# Sheet_1.net
KiCad netlist of a schematic drawn in Altium Designer
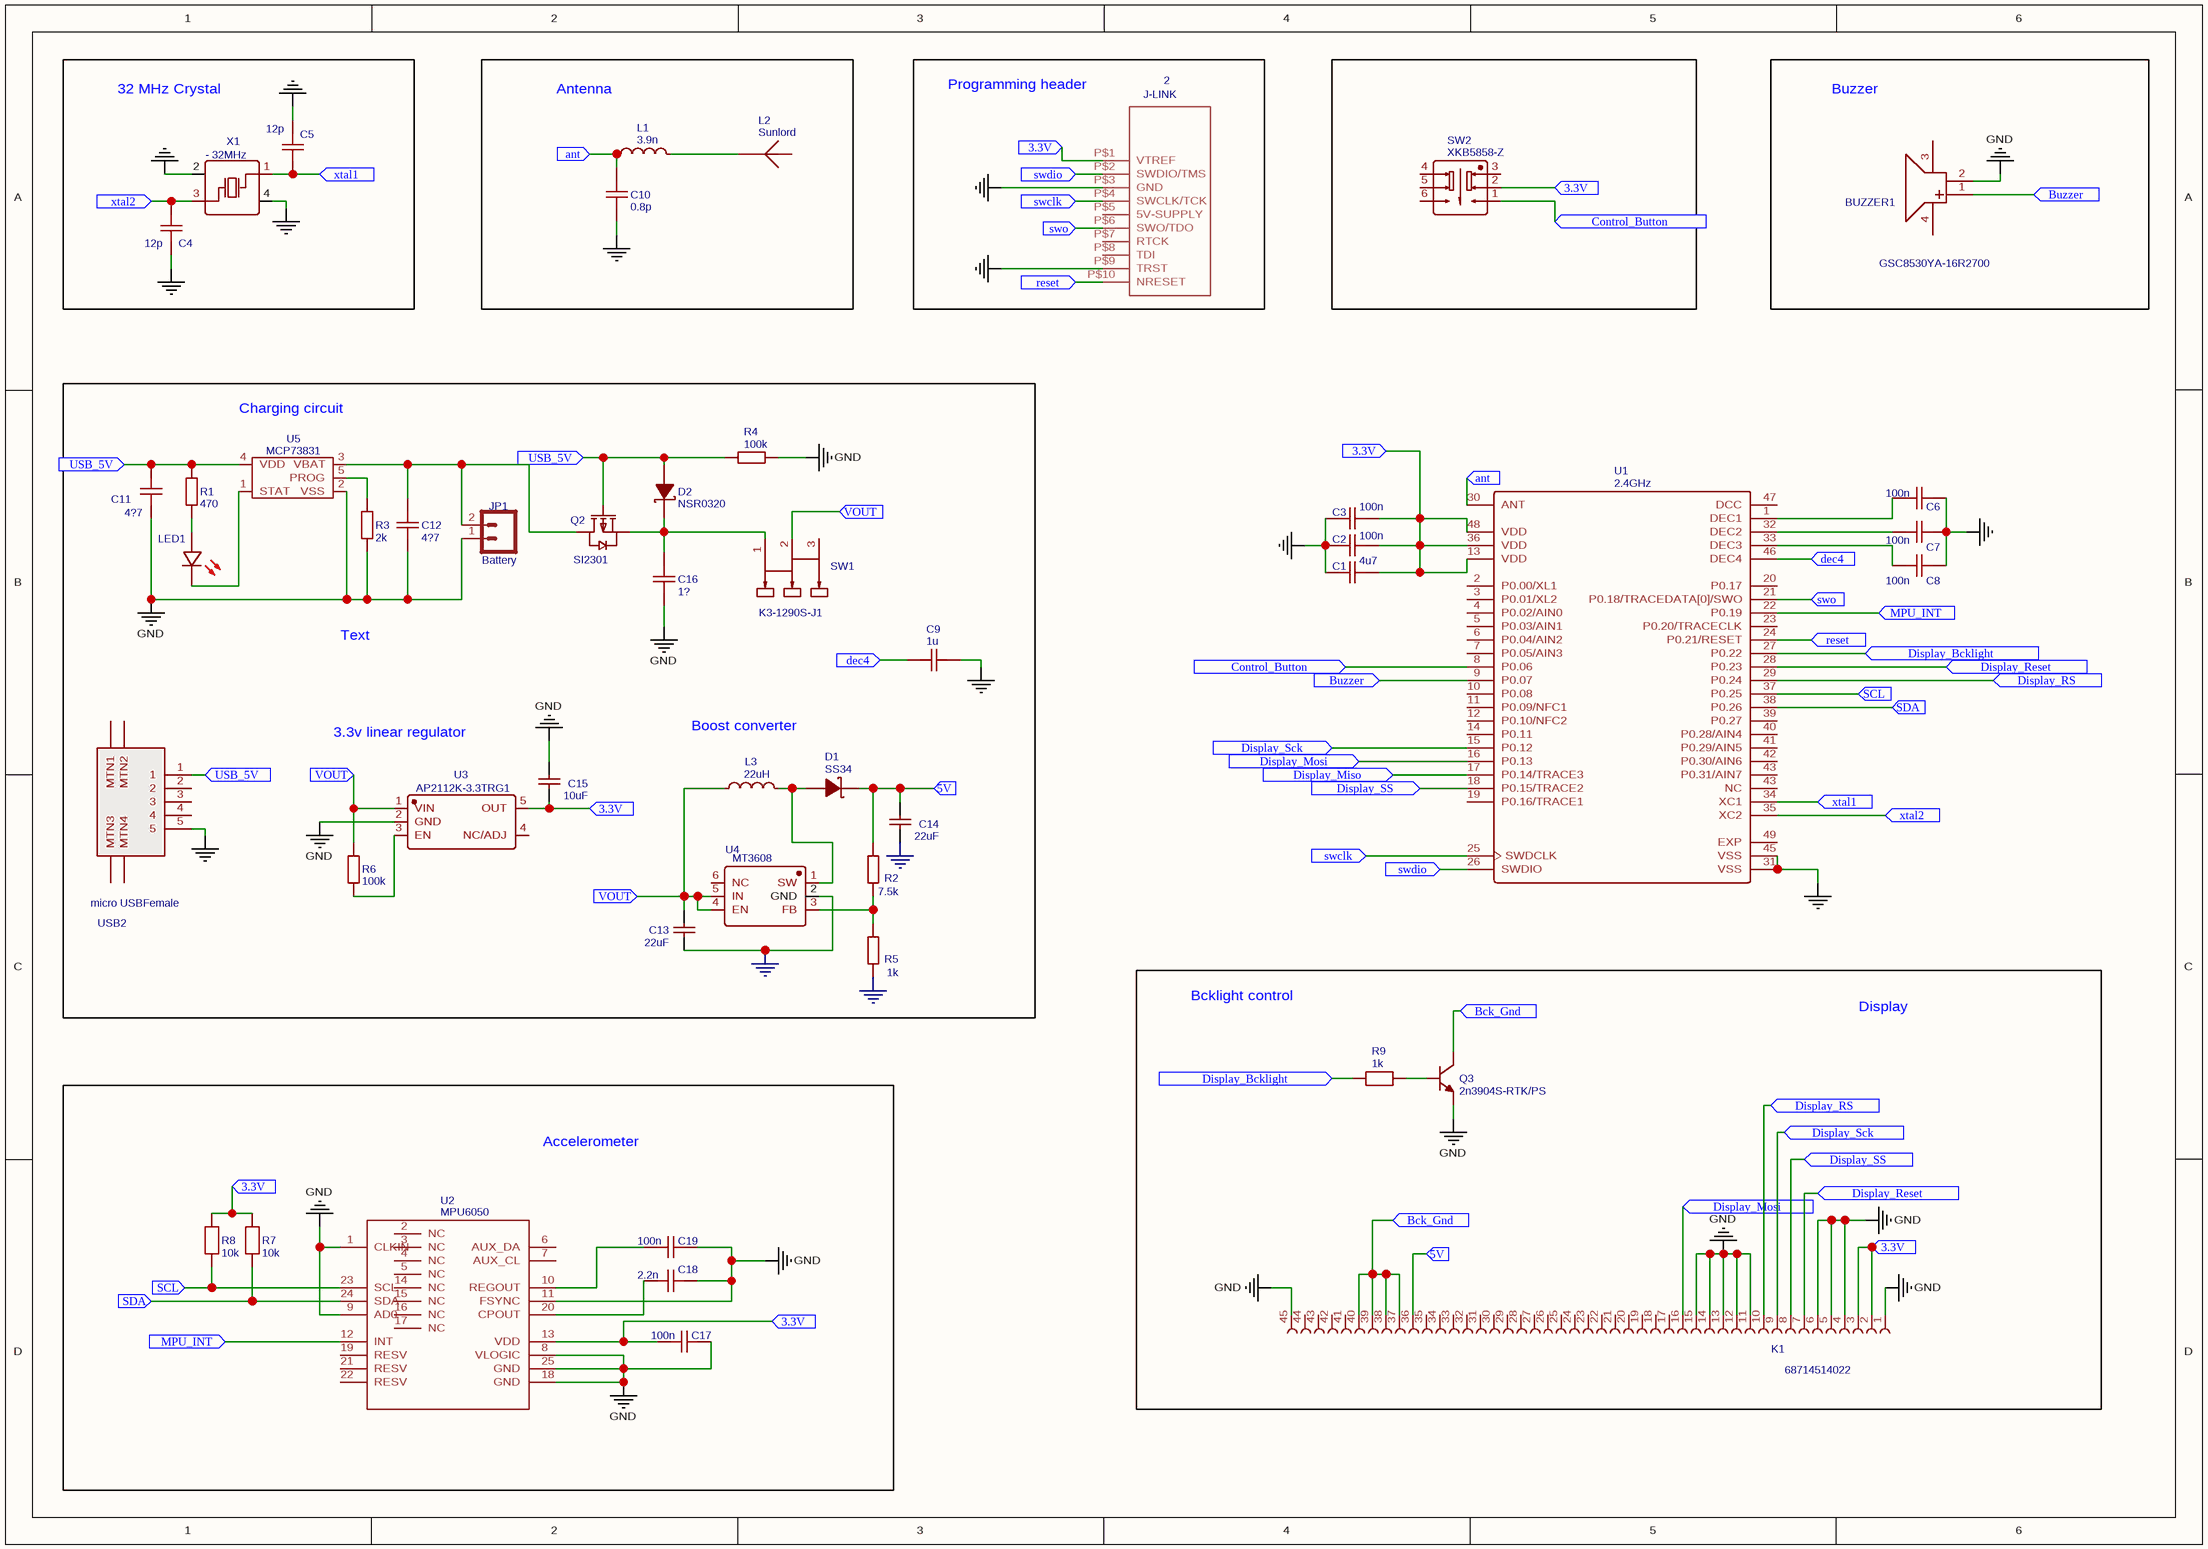
[diagram p0: Sheet_1.schdoc]

(export (version "E")
  (design (tool "Eeschema 10.0.6"))
  (components
    (comp (ref "2")
      (value "J-LINK")
      (fields (field (name "BOM_MANUFACTURER PART") "?") (field (name "CONTRIBUTOR") "Andrew D~{a}'Casto"))
      (libsource (lib "altium-import") (part "root_0_J-LINK_"))
    )
    (comp (ref "BUZZER1")
      (value "GSC8530YA-16R2700")
      (fields (field (name "BOM_SUPPLIER PART") "C255316") (field (name "CONTRIBUTOR") "LCSC"))
      (libsource (lib "altium-import") (part "root_0_GSC8530YA-16R2700_"))
    )
    (comp (ref "C1")
      (value "4u7")
      (fields (field (name "BOM_MANUFACTURER PART") "?"))
      (libsource (lib "altium-import") (part "root_3_4u7_"))
    )
    (comp (ref "C2")
      (value "100n")
      (fields (field (name "BOM_MANUFACTURER PART") "?"))
      (libsource (lib "altium-import") (part "root_3_100n_"))
    )
    (comp (ref "C3")
      (value "100n")
      (fields (field (name "BOM_MANUFACTURER PART") "?"))
      (libsource (lib "altium-import") (part "root_3_100n_"))
    )
    (comp (ref "C4")
      (value "12p")
      (fields (field (name "BOM_MANUFACTURER PART") "?"))
      (libsource (lib "altium-import") (part "root_0_12p_"))
    )
    (comp (ref "C5")
      (value "12p")
      (fields (field (name "BOM_MANUFACTURER PART") "?"))
      (libsource (lib "altium-import") (part "root_0_12p_"))
    )
    (comp (ref "C6")
      (value "100n")
      (fields (field (name "BOM_MANUFACTURER PART") "?"))
      (libsource (lib "altium-import") (part "root_1_100n_"))
    )
    (comp (ref "C7")
      (value "100n")
      (fields (field (name "BOM_MANUFACTURER PART") "?"))
      (libsource (lib "altium-import") (part "root_1_100n_"))
    )
    (comp (ref "C8")
      (value "100n")
      (fields (field (name "BOM_MANUFACTURER PART") "?"))
      (libsource (lib "altium-import") (part "root_1_100n_"))
    )
    (comp (ref "C9")
      (value "1u")
      (fields (field (name "BOM_MANUFACTURER PART") "?"))
      (libsource (lib "altium-import") (part "root_3_1u_"))
    )
    (comp (ref "C10")
      (value "0.8p")
      (fields (field (name "BOM_MANUFACTURER PART") "?"))
      (libsource (lib "altium-import") (part "root_0_0.8p_"))
    )
    (comp (ref "C11")
      (value "4?7")
      (fields (field (name "BOM_MANUFACTURER PART") "?"))
      (libsource (lib "altium-import") (part "root_0_4?7_"))
    )
    (comp (ref "C12")
      (value "4?7")
      (fields (field (name "BOM_MANUFACTURER PART") "?"))
      (libsource (lib "altium-import") (part "root_0_4?7_"))
    )
    (comp (ref "C13")
      (value "22uF")
      (fields
        (field (name "VOLTAGE") "25V")
        (field (name "TOLERANCE") "±10%")
        (field (name "BOM_MANUFACTURER PART") "1812X226K250NT")
      )
      (libsource (lib "altium-import") (part "root_1_22uF_"))
    )
    (comp (ref "C14")
      (value "22uF")
      (fields
        (field (name "VOLTAGE") "25V")
        (field (name "TOLERANCE") "±10%")
        (field (name "BOM_MANUFACTURER PART") "1812X226K250NT")
      )
      (libsource (lib "altium-import") (part "root_3_22uF_"))
    )
    (comp (ref "C15")
      (value "10uF")
      (fields
        (field (name "VOLTAGE") "25V")
        (field (name "TOLERANCE") "±10%")
        (field (name "BOM_MANUFACTURER PART") "1812X226K250NT")
      )
      (libsource (lib "altium-import") (part "root_3_10uF_"))
    )
    (comp (ref "C16")
      (value "1?")
      (fields (field (name "BOM_MANUFACTURER PART") "?"))
      (libsource (lib "altium-import") (part "root_0_1?_"))
    )
    (comp (ref "C17")
      (value "100n")
      (fields (field (name "BOM_MANUFACTURER PART") "?"))
      (libsource (lib "altium-import") (part "root_1_100n_"))
    )
    (comp (ref "C18")
      (value "2.2n")
      (fields (field (name "BOM_MANUFACTURER PART") "?"))
      (libsource (lib "altium-import") (part "root_1_2.2n_"))
    )
    (comp (ref "C19")
      (value "100n")
      (fields (field (name "BOM_MANUFACTURER PART") "?"))
      (libsource (lib "altium-import") (part "root_1_100n_"))
    )
    (comp (ref "D1")
      (value "SS34")
      (fields (field (name "BOM_SUPPLIER PART") "C8678"))
      (libsource (lib "altium-import") (part "root_0_SS34_"))
    )
    (comp (ref "D2")
      (value "NSR0320")
      (fields (field (name "BOM_MANUFACTURER PART") "?"))
      (libsource (lib "altium-import") (part "root_3_NSR0320_"))
    )
    (comp (ref "JP1")
      (value "Battery")
      (fields (field (name "BOM_MANUFACTURER PART") "?") (field (name "CONTRIBUTOR") "SparkFun"))
      (libsource (lib "altium-import") (part "root_2_Battery_"))
    )
    (comp (ref "K1")
      (value "68714514022")
      (description "WR-FPC 0.5mm SMT ZIF Horizontal Top Contact, 45 Pins=Code : Con_FPC_ZIF_0.50_68714514022")
      (fields (field (name "BOM_MANUFACTURER PART") "?"))
      (libsource (lib "altium-import") (part "root_3_68714514022_"))
    )
    (comp (ref "L1")
      (value "3.9n")
      (fields (field (name "BOM_MANUFACTURER PART") "?"))
      (libsource (lib "altium-import") (part "root_0_3.9n_"))
    )
    (comp (ref "L2")
      (value "Sunlord")
      (fields
        (field (name "BOM_SUPPLIER PART") "C279814")
        (field (name "BOM_MANUFACTURER PART") "SLDA52-2R540G-S1TF")
        (field (name "CONTRIBUTOR") "LCSC")
      )
      (libsource (lib "altium-import") (part "root_3_Sunlord_"))
    )
    (comp (ref "L3")
      (value "22uH")
      (fields
        (field (name "BOM_MANUFACTURER PART") "SMRH74-220MT")
        (field (name "BOM_SUPPLIER PART") "C27442")
      )
      (libsource (lib "altium-import") (part "root_0_22uH_"))
    )
    (comp (ref "LED1")
      (value "charge")
      (fields
        (field (name "BOM_SUPPLIER PART") "C131244")
        (field (name "BOM_MANUFACTURER PART") "17-21SURC/S530-A2/TR8")
      )
      (libsource (lib "altium-import") (part "root_3_charge_"))
    )
    (comp (ref "Q2") (value "SI2301") (libsource (lib "altium-import") (part "root_3_SI2301_")))
    (comp (ref "Q3")
      (value "2n3904S-RTK/PS")
      (fields (field (name "BOM_SUPPLIER PART") "C18536"))
      (libsource (lib "altium-import") (part "root_0_2n3904S-RTK/PS_"))
    )
    (comp (ref "R1")
      (value "470")
      (fields (field (name "BOM_MANUFACTURER PART") "?"))
      (libsource (lib "altium-import") (part "root_1_470_"))
    )
    (comp (ref "R2")
      (value "7.5k")
      (fields (field (name "BOM_MANUFACTURER PART") "?"))
      (libsource (lib "altium-import") (part "root_1_7.5k_"))
    )
    (comp (ref "R3")
      (value "2k")
      (fields (field (name "BOM_MANUFACTURER PART") "?"))
      (libsource (lib "altium-import") (part "root_1_2k_"))
    )
    (comp (ref "R4")
      (value "100k")
      (fields (field (name "BOM_MANUFACTURER PART") "?"))
      (libsource (lib "altium-import") (part "root_2_100k_"))
    )
    (comp (ref "R5")
      (value "1k")
      (fields (field (name "BOM_MANUFACTURER PART") "?"))
      (libsource (lib "altium-import") (part "root_1_1k_"))
    )
    (comp (ref "R6")
      (value "100k")
      (fields (field (name "BOM_MANUFACTURER PART") "?"))
      (libsource (lib "altium-import") (part "root_3_100k_"))
    )
    (comp (ref "R7")
      (value "10k")
      (fields (field (name "BOM_MANUFACTURER PART") "?"))
      (libsource (lib "altium-import") (part "root_1_10k_"))
    )
    (comp (ref "R8")
      (value "10k")
      (fields (field (name "BOM_MANUFACTURER PART") "?"))
      (libsource (lib "altium-import") (part "root_1_10k_"))
    )
    (comp (ref "R9")
      (value "1k")
      (fields (field (name "BOM_MANUFACTURER PART") "?"))
      (libsource (lib "altium-import") (part "root_0_1k_"))
    )
    (comp (ref "SW1")
      (value "K3-1290S-J1")
      (fields (field (name "BOM_SUPPLIER PART") "C223846") (field (name "CONTRIBUTOR") "LCSC"))
      (libsource (lib "altium-import") (part "root_0_K3-1290S-J1_"))
    )
    (comp (ref "SW2")
      (value "XKB5858-Z")
      (fields (field (name "BOM_SUPPLIER PART") "C318868") (field (name "CONTRIBUTOR") "LCSC"))
      (libsource (lib "altium-import") (part "root_1_XKB5858-Z_"))
    )
    (comp (ref "U1")
      (value "2.4GHz")
      (fields
        (field (name "BOM_MANUFACTURER PART") "NRF52832-QFAA-R")
        (field (name "BOM_SUPPLIER PART") "C77540")
      )
      (libsource (lib "altium-import") (part "root_0_2.4GHz_"))
    )
    (comp (ref "U2")
      (value "MPU6050")
      (fields (field (name "BOM_MANUFACTURER PART") "?"))
      (libsource (lib "altium-import") (part "root_0_MPU6050_"))
    )
    (comp (ref "U3")
      (value "AP2112K-3.3TRG1")
      (fields (field (name "BOM_SUPPLIER PART") "C51118") (field (name "CONTRIBUTOR") "LCSC"))
      (libsource (lib "altium-import") (part "root_0_AP2112K-3.3TRG1_"))
    )
    (comp (ref "U4")
      (value "MT3608")
      (fields (field (name "BOM_SUPPLIER PART") "C84817"))
      (libsource (lib "altium-import") (part "root_0_MT3608_"))
    )
    (comp (ref "U5")
      (value "MCP73831")
      (fields (field (name "BOM_MANUFACTURER PART") "?") (field (name "CONTRIBUTOR") "KiCad"))
      (libsource (lib "altium-import") (part "root_0_MCP73831_"))
    )
    (comp (ref "USB2")
      (value "micro USBFemale")
      (fields (field (name "BOM_SUPPLIER PART") "C10418"))
      (libsource (lib "altium-import") (part "root_0_micro USBFemale_"))
    )
    (comp (ref "X1")
      (value "- 32MHz")
      (fields
        (field (name "BOM_SUPPLIER PART") "C253733")
        (field (name "BOM_MANUFACTURER PART") "1XTV26000PEA")
        (field (name "CONTRIBUTOR") "LCSC")
      )
      (libsource (lib "altium-import") (part "root_2_- 32MHz_"))
    )
  )
  (nets
    (net (code "1") (name "/3.3V") (class "Default")
      (node (ref "2") (pin "P$1") (pinfunction "VTREF_P$1") (pintype "passive"))
      (node (ref "C1") (pin "2") (pinfunction "2_2") (pintype "passive"))
      (node (ref "C15") (pin "2") (pinfunction "2_2") (pintype "passive"))
      (node (ref "C17") (pin "2") (pinfunction "2_2") (pintype "passive"))
      (node (ref "C2") (pin "2") (pinfunction "2_2") (pintype "passive"))
      (node (ref "C3") (pin "2") (pinfunction "2_2") (pintype "passive"))
      (node (ref "K1") (pin "2") (pinfunction "2_2") (pintype "passive"))
      (node (ref "K1") (pin "3") (pinfunction "3_3") (pintype "passive"))
      (node (ref "R7") (pin "2") (pinfunction "2_2") (pintype "passive"))
      (node (ref "R8") (pin "2") (pinfunction "2_2") (pintype "passive"))
      (node (ref "SW2") (pin "2") (pinfunction "2_2") (pintype "passive"))
      (node (ref "U1") (pin "13") (pinfunction "VDD_13") (pintype "passive"))
      (node (ref "U1") (pin "36") (pinfunction "VDD_36") (pintype "passive"))
      (node (ref "U1") (pin "48") (pinfunction "VDD_48") (pintype "passive"))
      (node (ref "U2") (pin "13") (pinfunction "VDD_13") (pintype "passive"))
      (node (ref "U3") (pin "5") (pinfunction "OUT_5") (pintype "passive"))
    )
    (net (code "2") (name "/5V") (class "Default")
      (node (ref "C14") (pin "1") (pinfunction "1_1") (pintype "passive"))
      (node (ref "D1") (pin "2") (pinfunction "K_2") (pintype "passive"))
      (node (ref "K1") (pin "36") (pinfunction "36_36") (pintype "passive"))
      (node (ref "R2") (pin "2") (pinfunction "2_2") (pintype "passive"))
    )
    (net (code "3") (name "/Bck_Gnd") (class "Default")
      (node (ref "K1") (pin "37") (pinfunction "37_37") (pintype "passive"))
      (node (ref "K1") (pin "38") (pinfunction "38_38") (pintype "passive"))
      (node (ref "K1") (pin "39") (pinfunction "39_39") (pintype "passive"))
      (node (ref "K1") (pin "40") (pinfunction "40_40") (pintype "passive"))
      (node (ref "Q3") (pin "3") (pinfunction "C_3") (pintype "passive"))
    )
    (net (code "4") (name "/Buzzer") (class "Default")
      (node (ref "BUZZER1") (pin "1") (pinfunction "+_1") (pintype "passive"))
      (node (ref "U1") (pin "9") (pinfunction "P0.07_9") (pintype "passive"))
    )
    (net (code "5") (name "/Control_Button") (class "Default")
      (node (ref "SW2") (pin "1") (pinfunction "1_1") (pintype "passive"))
      (node (ref "U1") (pin "8") (pinfunction "P0.06_8") (pintype "passive"))
    )
    (net (code "6") (name "/Display_Bcklight") (class "Default")
      (node (ref "R9") (pin "1") (pinfunction "1_1") (pintype "passive"))
      (node (ref "U1") (pin "27") (pinfunction "P0.22_27") (pintype "passive"))
    )
    (net (code "7") (name "/Display_Miso") (class "Default")
      (node (ref "U1") (pin "17") (pinfunction "P0.14/TRACE3_17") (pintype "passive"))
    )
    (net (code "8") (name "/Display_Mosi") (class "Default")
      (node (ref "K1") (pin "16") (pinfunction "16_16") (pintype "passive"))
      (node (ref "U1") (pin "16") (pinfunction "P0.13_16") (pintype "passive"))
    )
    (net (code "9") (name "/Display_RS") (class "Default")
      (node (ref "K1") (pin "10") (pinfunction "10_10") (pintype "passive"))
      (node (ref "U1") (pin "29") (pinfunction "P0.24_29") (pintype "passive"))
    )
    (net (code "10") (name "/Display_Reset") (class "Default")
      (node (ref "K1") (pin "7") (pinfunction "7_7") (pintype "passive"))
      (node (ref "U1") (pin "28") (pinfunction "P0.23_28") (pintype "passive"))
    )
    (net (code "11") (name "/Display_SS") (class "Default")
      (node (ref "K1") (pin "8") (pinfunction "8_8") (pintype "passive"))
      (node (ref "U1") (pin "18") (pinfunction "P0.15/TRACE2_18") (pintype "passive"))
    )
    (net (code "12") (name "/Display_Sck") (class "Default")
      (node (ref "K1") (pin "9") (pinfunction "9_9") (pintype "passive"))
      (node (ref "U1") (pin "15") (pinfunction "P0.12_15") (pintype "passive"))
    )
    (net (code "13") (name "/MPU_INT") (class "Default")
      (node (ref "U1") (pin "22") (pinfunction "P0.19_22") (pintype "passive"))
      (node (ref "U2") (pin "12") (pinfunction "INT_12") (pintype "passive"))
    )
    (net (code "14") (name "/SCL") (class "Default")
      (node (ref "R8") (pin "1") (pinfunction "1_1") (pintype "passive"))
      (node (ref "U1") (pin "37") (pinfunction "P0.25_37") (pintype "passive"))
      (node (ref "U2") (pin "23") (pinfunction "SCL_23") (pintype "passive"))
    )
    (net (code "15") (name "/SDA") (class "Default")
      (node (ref "R7") (pin "1") (pinfunction "1_1") (pintype "passive"))
      (node (ref "U1") (pin "38") (pinfunction "P0.26_38") (pintype "passive"))
      (node (ref "U2") (pin "24") (pinfunction "SDA_24") (pintype "passive"))
    )
    (net (code "16") (name "/USB_5V") (class "Default")
      (node (ref "C11") (pin "2") (pinfunction "2_2") (pintype "passive"))
      (node (ref "D2") (pin "1") (pinfunction "A_1") (pintype "passive"))
      (node (ref "Q2") (pin "1") (pinfunction "G_1") (pintype "passive"))
      (node (ref "R1") (pin "2") (pinfunction "2_2") (pintype "passive"))
      (node (ref "R4") (pin "2") (pinfunction "2_2") (pintype "passive"))
      (node (ref "U5") (pin "4") (pinfunction "VDD_4") (pintype "passive"))
      (node (ref "USB2") (pin "1") (pinfunction "1_1") (pintype "passive"))
    )
    (net (code "17") (name "/VOUT") (class "Default")
      (node (ref "C13") (pin "2") (pinfunction "2_2") (pintype "passive"))
      (node (ref "L3") (pin "1") (pinfunction "1_1") (pintype "passive"))
      (node (ref "R6") (pin "1") (pinfunction "1_1") (pintype "passive"))
      (node (ref "SW1") (pin "2") (pinfunction "2_2") (pintype "passive"))
      (node (ref "U3") (pin "1") (pinfunction "VIN_1") (pintype "passive"))
      (node (ref "U4") (pin "4") (pinfunction "EN_4") (pintype "passive"))
      (node (ref "U4") (pin "5") (pinfunction "IN_5") (pintype "passive"))
    )
    (net (code "18") (name "/ant") (class "Default")
      (node (ref "C10") (pin "2") (pinfunction "2_2") (pintype "passive"))
      (node (ref "L1") (pin "1") (pinfunction "1_1") (pintype "passive"))
      (node (ref "U1") (pin "30") (pinfunction "ANT_30") (pintype "passive"))
    )
    (net (code "19") (name "/dec4") (class "Default")
      (node (ref "C9") (pin "1") (pinfunction "1_1") (pintype "passive"))
      (node (ref "U1") (pin "46") (pinfunction "DEC4_46") (pintype "passive"))
    )
    (net (code "20") (name "/reset") (class "Default")
      (node (ref "2") (pin "P$10") (pinfunction "NRESET_P$10") (pintype "passive"))
      (node (ref "U1") (pin "24") (pinfunction "P0.21/RESET_24") (pintype "passive"))
    )
    (net (code "21") (name "/swclk") (class "Default")
      (node (ref "2") (pin "P$4") (pinfunction "SWCLK/TCK_P$4") (pintype "passive"))
      (node (ref "U1") (pin "25") (pinfunction "SWDCLK_25") (pintype "passive"))
    )
    (net (code "22") (name "/swdio") (class "Default")
      (node (ref "2") (pin "P$2") (pinfunction "SWDIO/TMS_P$2") (pintype "passive"))
      (node (ref "U1") (pin "26") (pinfunction "SWDIO_26") (pintype "passive"))
    )
    (net (code "23") (name "/swo") (class "Default")
      (node (ref "2") (pin "P$6") (pinfunction "SWO/TDO_P$6") (pintype "passive"))
      (node (ref "U1") (pin "21") (pinfunction "P0.18/TRACEDATA[0]/SWO_21") (pintype "passive"))
    )
    (net (code "24") (name "/xtal1") (class "Default")
      (node (ref "C5") (pin "1") (pinfunction "1_1") (pintype "passive"))
      (node (ref "U1") (pin "34") (pinfunction "XC1_34") (pintype "passive"))
      (node (ref "X1") (pin "1") (pinfunction "OSC1_1") (pintype "passive"))
    )
    (net (code "25") (name "/xtal2") (class "Default")
      (node (ref "C4") (pin "2") (pinfunction "2_2") (pintype "passive"))
      (node (ref "U1") (pin "35") (pinfunction "XC2_35") (pintype "passive"))
      (node (ref "X1") (pin "3") (pinfunction "OSC2_3") (pintype "passive"))
    )
    (net (code "26") (name "GND") (class "Default")
      (node (ref "2") (pin "P$3") (pinfunction "GND_P$3") (pintype "passive"))
      (node (ref "2") (pin "P$9") (pinfunction "TRST_P$9") (pintype "passive"))
      (node (ref "BUZZER1") (pin "2") (pinfunction "-_2") (pintype "passive"))
      (node (ref "C1") (pin "1") (pinfunction "1_1") (pintype "passive"))
      (node (ref "C10") (pin "1") (pinfunction "1_1") (pintype "passive"))
      (node (ref "C11") (pin "1") (pinfunction "1_1") (pintype "passive"))
      (node (ref "C12") (pin "1") (pinfunction "1_1") (pintype "passive"))
      (node (ref "C13") (pin "1") (pinfunction "1_1") (pintype "passive"))
      (node (ref "C14") (pin "2") (pinfunction "2_2") (pintype "passive"))
      (node (ref "C15") (pin "1") (pinfunction "1_1") (pintype "passive"))
      (node (ref "C16") (pin "1") (pinfunction "1_1") (pintype "passive"))
      (node (ref "C17") (pin "1") (pinfunction "1_1") (pintype "passive"))
      (node (ref "C18") (pin "1") (pinfunction "1_1") (pintype "passive"))
      (node (ref "C19") (pin "1") (pinfunction "1_1") (pintype "passive"))
      (node (ref "C2") (pin "1") (pinfunction "1_1") (pintype "passive"))
      (node (ref "C3") (pin "1") (pinfunction "1_1") (pintype "passive"))
      (node (ref "C4") (pin "1") (pinfunction "1_1") (pintype "passive"))
      (node (ref "C5") (pin "2") (pinfunction "2_2") (pintype "passive"))
      (node (ref "C6") (pin "1") (pinfunction "1_1") (pintype "passive"))
      (node (ref "C7") (pin "1") (pinfunction "1_1") (pintype "passive"))
      (node (ref "C8") (pin "1") (pinfunction "1_1") (pintype "passive"))
      (node (ref "C9") (pin "2") (pinfunction "2_2") (pintype "passive"))
      (node (ref "JP1") (pin "1") (pinfunction "2_1") (pintype "passive"))
      (node (ref "K1") (pin "1") (pinfunction "1_1") (pintype "passive"))
      (node (ref "K1") (pin "11") (pinfunction "11_11") (pintype "passive"))
      (node (ref "K1") (pin "12") (pinfunction "12_12") (pintype "passive"))
      (node (ref "K1") (pin "13") (pinfunction "13_13") (pintype "passive"))
      (node (ref "K1") (pin "14") (pinfunction "14_14") (pintype "passive"))
      (node (ref "K1") (pin "15") (pinfunction "15_15") (pintype "passive"))
      (node (ref "K1") (pin "4") (pinfunction "4_4") (pintype "passive"))
      (node (ref "K1") (pin "45") (pinfunction "45_45") (pintype "passive"))
      (node (ref "K1") (pin "5") (pinfunction "5_5") (pintype "passive"))
      (node (ref "K1") (pin "6") (pinfunction "6_6") (pintype "passive"))
      (node (ref "Q3") (pin "1") (pinfunction "E_1") (pintype "passive"))
      (node (ref "R3") (pin "1") (pinfunction "1_1") (pintype "passive"))
      (node (ref "R4") (pin "1") (pinfunction "1_1") (pintype "passive"))
      (node (ref "R5") (pin "1") (pinfunction "1_1") (pintype "passive"))
      (node (ref "U1") (pin "31") (pinfunction "VSS_31") (pintype "passive"))
      (node (ref "U1") (pin "45") (pinfunction "VSS_45") (pintype "passive"))
      (node (ref "U2") (pin "1") (pinfunction "CLKIN_1") (pintype "passive"))
      (node (ref "U2") (pin "11") (pinfunction "FSYNC_11") (pintype "passive"))
      (node (ref "U2") (pin "18") (pinfunction "GND_18") (pintype "passive"))
      (node (ref "U2") (pin "25") (pinfunction "GND_25") (pintype "passive"))
      (node (ref "U2") (pin "8") (pinfunction "VLOGIC_8") (pintype "passive"))
      (node (ref "U2") (pin "9") (pinfunction "AD0_9") (pintype "passive"))
      (node (ref "U3") (pin "2") (pinfunction "GND_2") (pintype "passive"))
      (node (ref "U4") (pin "2") (pinfunction "GND_2") (pintype "passive"))
      (node (ref "U5") (pin "2") (pinfunction "VSS_2") (pintype "passive"))
      (node (ref "USB2") (pin "5") (pinfunction "5_5") (pintype "passive"))
      (node (ref "X1") (pin "2") (pinfunction "GND_2") (pintype "passive"))
      (node (ref "X1") (pin "4") (pinfunction "GND_4") (pintype "passive"))
    )
    (net (code "27") (name "Net-(D1-A)") (class "Default")
      (node (ref "D1") (pin "1") (pinfunction "A_1") (pintype "passive"))
      (node (ref "L3") (pin "2") (pinfunction "2_2") (pintype "passive"))
      (node (ref "U4") (pin "1") (pinfunction "SW_1") (pintype "passive"))
    )
    (net (code "28") (name "Net-(D2-K)") (class "Default")
      (node (ref "C16") (pin "2") (pinfunction "2_2") (pintype "passive"))
      (node (ref "D2") (pin "2") (pinfunction "K_2") (pintype "passive"))
      (node (ref "Q2") (pin "2") (pinfunction "S_2") (pintype "passive"))
      (node (ref "SW1") (pin "1") (pinfunction "1_1") (pintype "passive"))
    )
    (net (code "29") (name "Net-(JP1-1)") (class "Default")
      (node (ref "C12") (pin "2") (pinfunction "2_2") (pintype "passive"))
      (node (ref "JP1") (pin "2") (pinfunction "1_2") (pintype "passive"))
      (node (ref "Q2") (pin "3") (pinfunction "D_3") (pintype "passive"))
      (node (ref "U5") (pin "3") (pinfunction "VBAT_3") (pintype "passive"))
    )
    (net (code "30") (name "Net-(L1-Pad2)") (class "Default")
      (node (ref "L1") (pin "2") (pinfunction "2_2") (pintype "passive"))
      (node (ref "L2") (pin "ANT") (pinfunction "ANT_ANT") (pintype "passive"))
    )
    (net (code "31") (name "Net-(LED1-+)") (class "Default")
      (node (ref "LED1") (pin "1") (pinfunction "+_1") (pintype "passive"))
      (node (ref "R1") (pin "1") (pinfunction "1_1") (pintype "passive"))
    )
    (net (code "32") (name "Net-(LED1--)") (class "Default")
      (node (ref "LED1") (pin "2") (pinfunction "-_2") (pintype "passive"))
      (node (ref "U5") (pin "1") (pinfunction "STAT_1") (pintype "passive"))
    )
    (net (code "33") (name "Net-(Q3-B)") (class "Default")
      (node (ref "Q3") (pin "2") (pinfunction "B_2") (pintype "passive"))
      (node (ref "R9") (pin "2") (pinfunction "2_2") (pintype "passive"))
    )
    (net (code "34") (name "Net-(U1-DEC1)") (class "Default")
      (node (ref "C6") (pin "2") (pinfunction "2_2") (pintype "passive"))
      (node (ref "U1") (pin "1") (pinfunction "DEC1_1") (pintype "passive"))
    )
    (net (code "35") (name "Net-(U1-DEC2)") (class "Default")
      (node (ref "C7") (pin "2") (pinfunction "2_2") (pintype "passive"))
      (node (ref "U1") (pin "32") (pinfunction "DEC2_32") (pintype "passive"))
    )
    (net (code "36") (name "Net-(U1-DEC3)") (class "Default")
      (node (ref "C8") (pin "2") (pinfunction "2_2") (pintype "passive"))
      (node (ref "U1") (pin "33") (pinfunction "DEC3_33") (pintype "passive"))
    )
    (net (code "37") (name "Net-(U2-CPOUT)") (class "Default")
      (node (ref "C18") (pin "2") (pinfunction "2_2") (pintype "passive"))
      (node (ref "U2") (pin "20") (pinfunction "CPOUT_20") (pintype "passive"))
    )
    (net (code "38") (name "Net-(U2-REGOUT)") (class "Default")
      (node (ref "C19") (pin "2") (pinfunction "2_2") (pintype "passive"))
      (node (ref "U2") (pin "10") (pinfunction "REGOUT_10") (pintype "passive"))
    )
    (net (code "39") (name "Net-(U3-EN)") (class "Default")
      (node (ref "R6") (pin "2") (pinfunction "2_2") (pintype "passive"))
      (node (ref "U3") (pin "3") (pinfunction "EN_3") (pintype "passive"))
    )
    (net (code "40") (name "Net-(U4-FB)") (class "Default")
      (node (ref "R2") (pin "1") (pinfunction "1_1") (pintype "passive"))
      (node (ref "R5") (pin "2") (pinfunction "2_2") (pintype "passive"))
      (node (ref "U4") (pin "3") (pinfunction "FB_3") (pintype "passive"))
    )
    (net (code "41") (name "Net-(U5-PROG)") (class "Default")
      (node (ref "R3") (pin "2") (pinfunction "2_2") (pintype "passive"))
      (node (ref "U5") (pin "5") (pinfunction "PROG_5") (pintype "passive"))
    )
    (net (code "42") (name "unconnected-(2-5V-SUPPLY-PadP$5)") (class "Default")
      (node (ref "2") (pin "P$5") (pinfunction "5V-SUPPLY_P$5") (pintype "passive"))
    )
    (net (code "43") (name "unconnected-(2-RTCK-PadP$7)") (class "Default")
      (node (ref "2") (pin "P$7") (pinfunction "RTCK_P$7") (pintype "passive"))
    )
    (net (code "44") (name "unconnected-(2-TDI-PadP$8)") (class "Default")
      (node (ref "2") (pin "P$8") (pinfunction "TDI_P$8") (pintype "passive"))
    )
    (net (code "45") (name "unconnected-(BUZZER1-Pad3)") (class "Default")
      (node (ref "BUZZER1") (pin "3") (pinfunction "3_3") (pintype "passive"))
    )
    (net (code "46") (name "unconnected-(BUZZER1-Pad4)") (class "Default")
      (node (ref "BUZZER1") (pin "4") (pinfunction "4_4") (pintype "passive"))
    )
    (net (code "47") (name "unconnected-(K1-Pad17)") (class "Default")
      (node (ref "K1") (pin "17") (pinfunction "17_17") (pintype "passive"))
    )
    (net (code "48") (name "unconnected-(K1-Pad18)") (class "Default")
      (node (ref "K1") (pin "18") (pinfunction "18_18") (pintype "passive"))
    )
    (net (code "49") (name "unconnected-(K1-Pad19)") (class "Default")
      (node (ref "K1") (pin "19") (pinfunction "19_19") (pintype "passive"))
    )
    (net (code "50") (name "unconnected-(K1-Pad20)") (class "Default")
      (node (ref "K1") (pin "20") (pinfunction "20_20") (pintype "passive"))
    )
    (net (code "51") (name "unconnected-(K1-Pad21)") (class "Default")
      (node (ref "K1") (pin "21") (pinfunction "21_21") (pintype "passive"))
    )
    (net (code "52") (name "unconnected-(K1-Pad22)") (class "Default")
      (node (ref "K1") (pin "22") (pinfunction "22_22") (pintype "passive"))
    )
    (net (code "53") (name "unconnected-(K1-Pad23)") (class "Default")
      (node (ref "K1") (pin "23") (pinfunction "23_23") (pintype "passive"))
    )
    (net (code "54") (name "unconnected-(K1-Pad24)") (class "Default")
      (node (ref "K1") (pin "24") (pinfunction "24_24") (pintype "passive"))
    )
    (net (code "55") (name "unconnected-(K1-Pad25)") (class "Default")
      (node (ref "K1") (pin "25") (pinfunction "25_25") (pintype "passive"))
    )
    (net (code "56") (name "unconnected-(K1-Pad26)") (class "Default")
      (node (ref "K1") (pin "26") (pinfunction "26_26") (pintype "passive"))
    )
    (net (code "57") (name "unconnected-(K1-Pad27)") (class "Default")
      (node (ref "K1") (pin "27") (pinfunction "27_27") (pintype "passive"))
    )
    (net (code "58") (name "unconnected-(K1-Pad28)") (class "Default")
      (node (ref "K1") (pin "28") (pinfunction "28_28") (pintype "passive"))
    )
    (net (code "59") (name "unconnected-(K1-Pad29)") (class "Default")
      (node (ref "K1") (pin "29") (pinfunction "29_29") (pintype "passive"))
    )
    (net (code "60") (name "unconnected-(K1-Pad30)") (class "Default")
      (node (ref "K1") (pin "30") (pinfunction "30_30") (pintype "passive"))
    )
    (net (code "61") (name "unconnected-(K1-Pad31)") (class "Default")
      (node (ref "K1") (pin "31") (pinfunction "31_31") (pintype "passive"))
    )
    (net (code "62") (name "unconnected-(K1-Pad32)") (class "Default")
      (node (ref "K1") (pin "32") (pinfunction "32_32") (pintype "passive"))
    )
    (net (code "63") (name "unconnected-(K1-Pad33)") (class "Default")
      (node (ref "K1") (pin "33") (pinfunction "33_33") (pintype "passive"))
    )
    (net (code "64") (name "unconnected-(K1-Pad34)") (class "Default")
      (node (ref "K1") (pin "34") (pinfunction "34_34") (pintype "passive"))
    )
    (net (code "65") (name "unconnected-(K1-Pad35)") (class "Default")
      (node (ref "K1") (pin "35") (pinfunction "35_35") (pintype "passive"))
    )
    (net (code "66") (name "unconnected-(K1-Pad41)") (class "Default")
      (node (ref "K1") (pin "41") (pinfunction "41_41") (pintype "passive"))
    )
    (net (code "67") (name "unconnected-(K1-Pad42)") (class "Default")
      (node (ref "K1") (pin "42") (pinfunction "42_42") (pintype "passive"))
    )
    (net (code "68") (name "unconnected-(K1-Pad43)") (class "Default")
      (node (ref "K1") (pin "43") (pinfunction "43_43") (pintype "passive"))
    )
    (net (code "69") (name "unconnected-(K1-Pad44)") (class "Default")
      (node (ref "K1") (pin "44") (pinfunction "44_44") (pintype "passive"))
    )
    (net (code "70") (name "unconnected-(L2-Pad2)") (class "Default")
      (node (ref "L2") (pin "2") (pinfunction "2_2") (pintype "passive"))
    )
    (net (code "71") (name "unconnected-(SW1-Pad3)") (class "Default")
      (node (ref "SW1") (pin "3") (pinfunction "3_3") (pintype "passive"))
    )
    (net (code "72") (name "unconnected-(SW2-Pad3)") (class "Default")
      (node (ref "SW2") (pin "3") (pinfunction "3_3") (pintype "passive"))
    )
    (net (code "73") (name "unconnected-(SW2-Pad4)") (class "Default")
      (node (ref "SW2") (pin "4") (pinfunction "4_4") (pintype "passive"))
    )
    (net (code "74") (name "unconnected-(SW2-Pad5)") (class "Default")
      (node (ref "SW2") (pin "5") (pinfunction "5_5") (pintype "passive"))
    )
    (net (code "75") (name "unconnected-(SW2-Pad6)") (class "Default")
      (node (ref "SW2") (pin "6") (pinfunction "6_6") (pintype "passive"))
    )
    (net (code "76") (name "unconnected-(U1-DCC-Pad47)") (class "Default")
      (node (ref "U1") (pin "47") (pinfunction "DCC_47") (pintype "passive"))
    )
    (net (code "77") (name "unconnected-(U1-EXP-Pad49)") (class "Default")
      (node (ref "U1") (pin "49") (pinfunction "EXP_49") (pintype "passive"))
    )
    (net (code "78") (name "unconnected-(U1-NC-Pad43)") (class "Default")
      (node (ref "U1") (pin "43") (pinfunction "NC_43") (pintype "passive"))
    )
    (net (code "79") (name "unconnected-(U1-P0.00{slash}XL1-Pad2)") (class "Default")
      (node (ref "U1") (pin "2") (pinfunction "P0.00/XL1_2") (pintype "passive"))
    )
    (net (code "80") (name "unconnected-(U1-P0.01{slash}XL2-Pad3)") (class "Default")
      (node (ref "U1") (pin "3") (pinfunction "P0.01/XL2_3") (pintype "passive"))
    )
    (net (code "81") (name "unconnected-(U1-P0.02{slash}AIN0-Pad4)") (class "Default")
      (node (ref "U1") (pin "4") (pinfunction "P0.02/AIN0_4") (pintype "passive"))
    )
    (net (code "82") (name "unconnected-(U1-P0.03{slash}AIN1-Pad5)") (class "Default")
      (node (ref "U1") (pin "5") (pinfunction "P0.03/AIN1_5") (pintype "passive"))
    )
    (net (code "83") (name "unconnected-(U1-P0.04{slash}AIN2-Pad6)") (class "Default")
      (node (ref "U1") (pin "6") (pinfunction "P0.04/AIN2_6") (pintype "passive"))
    )
    (net (code "84") (name "unconnected-(U1-P0.05{slash}AIN3-Pad7)") (class "Default")
      (node (ref "U1") (pin "7") (pinfunction "P0.05/AIN3_7") (pintype "passive"))
    )
    (net (code "85") (name "unconnected-(U1-P0.08-Pad10)") (class "Default")
      (node (ref "U1") (pin "10") (pinfunction "P0.08_10") (pintype "passive"))
    )
    (net (code "86") (name "unconnected-(U1-P0.09{slash}NFC1-Pad11)") (class "Default")
      (node (ref "U1") (pin "11") (pinfunction "P0.09/NFC1_11") (pintype "passive"))
    )
    (net (code "87") (name "unconnected-(U1-P0.10{slash}NFC2-Pad12)") (class "Default")
      (node (ref "U1") (pin "12") (pinfunction "P0.10/NFC2_12") (pintype "passive"))
    )
    (net (code "88") (name "unconnected-(U1-P0.11-Pad14)") (class "Default")
      (node (ref "U1") (pin "14") (pinfunction "P0.11_14") (pintype "passive"))
    )
    (net (code "89") (name "unconnected-(U1-P0.16{slash}TRACE1-Pad19)") (class "Default")
      (node (ref "U1") (pin "19") (pinfunction "P0.16/TRACE1_19") (pintype "passive"))
    )
    (net (code "90") (name "unconnected-(U1-P0.17-Pad20)") (class "Default")
      (node (ref "U1") (pin "20") (pinfunction "P0.17_20") (pintype "passive"))
    )
    (net (code "91") (name "unconnected-(U1-P0.20{slash}TRACECLK-Pad23)") (class "Default")
      (node (ref "U1") (pin "23") (pinfunction "P0.20/TRACECLK_23") (pintype "passive"))
    )
    (net (code "92") (name "unconnected-(U1-P0.27-Pad39)") (class "Default")
      (node (ref "U1") (pin "39") (pinfunction "P0.27_39") (pintype "passive"))
    )
    (net (code "93") (name "unconnected-(U1-P0.28{slash}AIN4-Pad40)") (class "Default")
      (node (ref "U1") (pin "40") (pinfunction "P0.28/AIN4_40") (pintype "passive"))
    )
    (net (code "94") (name "unconnected-(U1-P0.29{slash}AIN5-Pad41)") (class "Default")
      (node (ref "U1") (pin "41") (pinfunction "P0.29/AIN5_41") (pintype "passive"))
    )
    (net (code "95") (name "unconnected-(U1-P0.30{slash}AIN6-Pad42)") (class "Default")
      (node (ref "U1") (pin "42") (pinfunction "P0.30/AIN6_42") (pintype "passive"))
    )
    (net (code "96") (name "unconnected-(U1-P0.31{slash}AIN7-Pad43)") (class "Default")
      (node (ref "U1") (pin "43") (pinfunction "P0.31/AIN7_43") (pintype "passive"))
    )
    (net (code "97") (name "unconnected-(U2-AUX_CL-Pad7)") (class "Default")
      (node (ref "U2") (pin "7") (pinfunction "AUX_CL_7") (pintype "passive"))
    )
    (net (code "98") (name "unconnected-(U2-AUX_DA-Pad6)") (class "Default")
      (node (ref "U2") (pin "6") (pinfunction "AUX_DA_6") (pintype "passive"))
    )
    (net (code "99") (name "unconnected-(U2-NC-Pad2)") (class "Default")
      (node (ref "U2") (pin "2") (pinfunction "NC_2") (pintype "passive"))
    )
    (net (code "100") (name "unconnected-(U2-NC-Pad3)") (class "Default")
      (node (ref "U2") (pin "3") (pinfunction "NC_3") (pintype "passive"))
    )
    (net (code "101") (name "unconnected-(U2-NC-Pad4)") (class "Default")
      (node (ref "U2") (pin "4") (pinfunction "NC_4") (pintype "passive"))
    )
    (net (code "102") (name "unconnected-(U2-NC-Pad5)") (class "Default")
      (node (ref "U2") (pin "5") (pinfunction "NC_5") (pintype "passive"))
    )
    (net (code "103") (name "unconnected-(U2-NC-Pad14)") (class "Default")
      (node (ref "U2") (pin "14") (pinfunction "NC_14") (pintype "passive"))
    )
    (net (code "104") (name "unconnected-(U2-NC-Pad15)") (class "Default")
      (node (ref "U2") (pin "15") (pinfunction "NC_15") (pintype "passive"))
    )
    (net (code "105") (name "unconnected-(U2-NC-Pad16)") (class "Default")
      (node (ref "U2") (pin "16") (pinfunction "NC_16") (pintype "passive"))
    )
    (net (code "106") (name "unconnected-(U2-NC-Pad17)") (class "Default")
      (node (ref "U2") (pin "17") (pinfunction "NC_17") (pintype "passive"))
    )
    (net (code "107") (name "unconnected-(U2-RESV-Pad19)") (class "Default")
      (node (ref "U2") (pin "19") (pinfunction "RESV_19") (pintype "passive"))
    )
    (net (code "108") (name "unconnected-(U2-RESV-Pad21)") (class "Default")
      (node (ref "U2") (pin "21") (pinfunction "RESV_21") (pintype "passive"))
    )
    (net (code "109") (name "unconnected-(U2-RESV-Pad22)") (class "Default")
      (node (ref "U2") (pin "22") (pinfunction "RESV_22") (pintype "passive"))
    )
    (net (code "110") (name "unconnected-(U3-NC{slash}ADJ-Pad4)") (class "Default")
      (node (ref "U3") (pin "4") (pinfunction "NC/ADJ_4") (pintype "passive"))
    )
    (net (code "111") (name "unconnected-(U4-NC-Pad6)") (class "Default")
      (node (ref "U4") (pin "6") (pinfunction "NC_6") (pintype "passive"))
    )
    (net (code "112") (name "unconnected-(USB2-MTN1-Pad0)") (class "Default")
      (node (ref "USB2") (pin "0") (pinfunction "MTN1_0") (pintype "passive"))
    )
    (net (code "113") (name "unconnected-(USB2-MTN2-Pad0)") (class "Default")
      (node (ref "USB2") (pin "0") (pinfunction "MTN2_0") (pintype "passive"))
    )
    (net (code "114") (name "unconnected-(USB2-MTN3-Pad0)") (class "Default")
      (node (ref "USB2") (pin "0") (pinfunction "MTN3_0") (pintype "passive"))
    )
    (net (code "115") (name "unconnected-(USB2-MTN4-Pad0)") (class "Default")
      (node (ref "USB2") (pin "0") (pinfunction "MTN4_0") (pintype "passive"))
    )
    (net (code "116") (name "unconnected-(USB2-Pad2)") (class "Default")
      (node (ref "USB2") (pin "2") (pinfunction "2_2") (pintype "passive"))
    )
    (net (code "117") (name "unconnected-(USB2-Pad3)") (class "Default")
      (node (ref "USB2") (pin "3") (pinfunction "3_3") (pintype "passive"))
    )
    (net (code "118") (name "unconnected-(USB2-Pad4)") (class "Default")
      (node (ref "USB2") (pin "4") (pinfunction "4_4") (pintype "passive"))
    )
  )
)
